# CH32X035F8U6-R0.net
KiCad netlist of a schematic drawn in Altium Designer
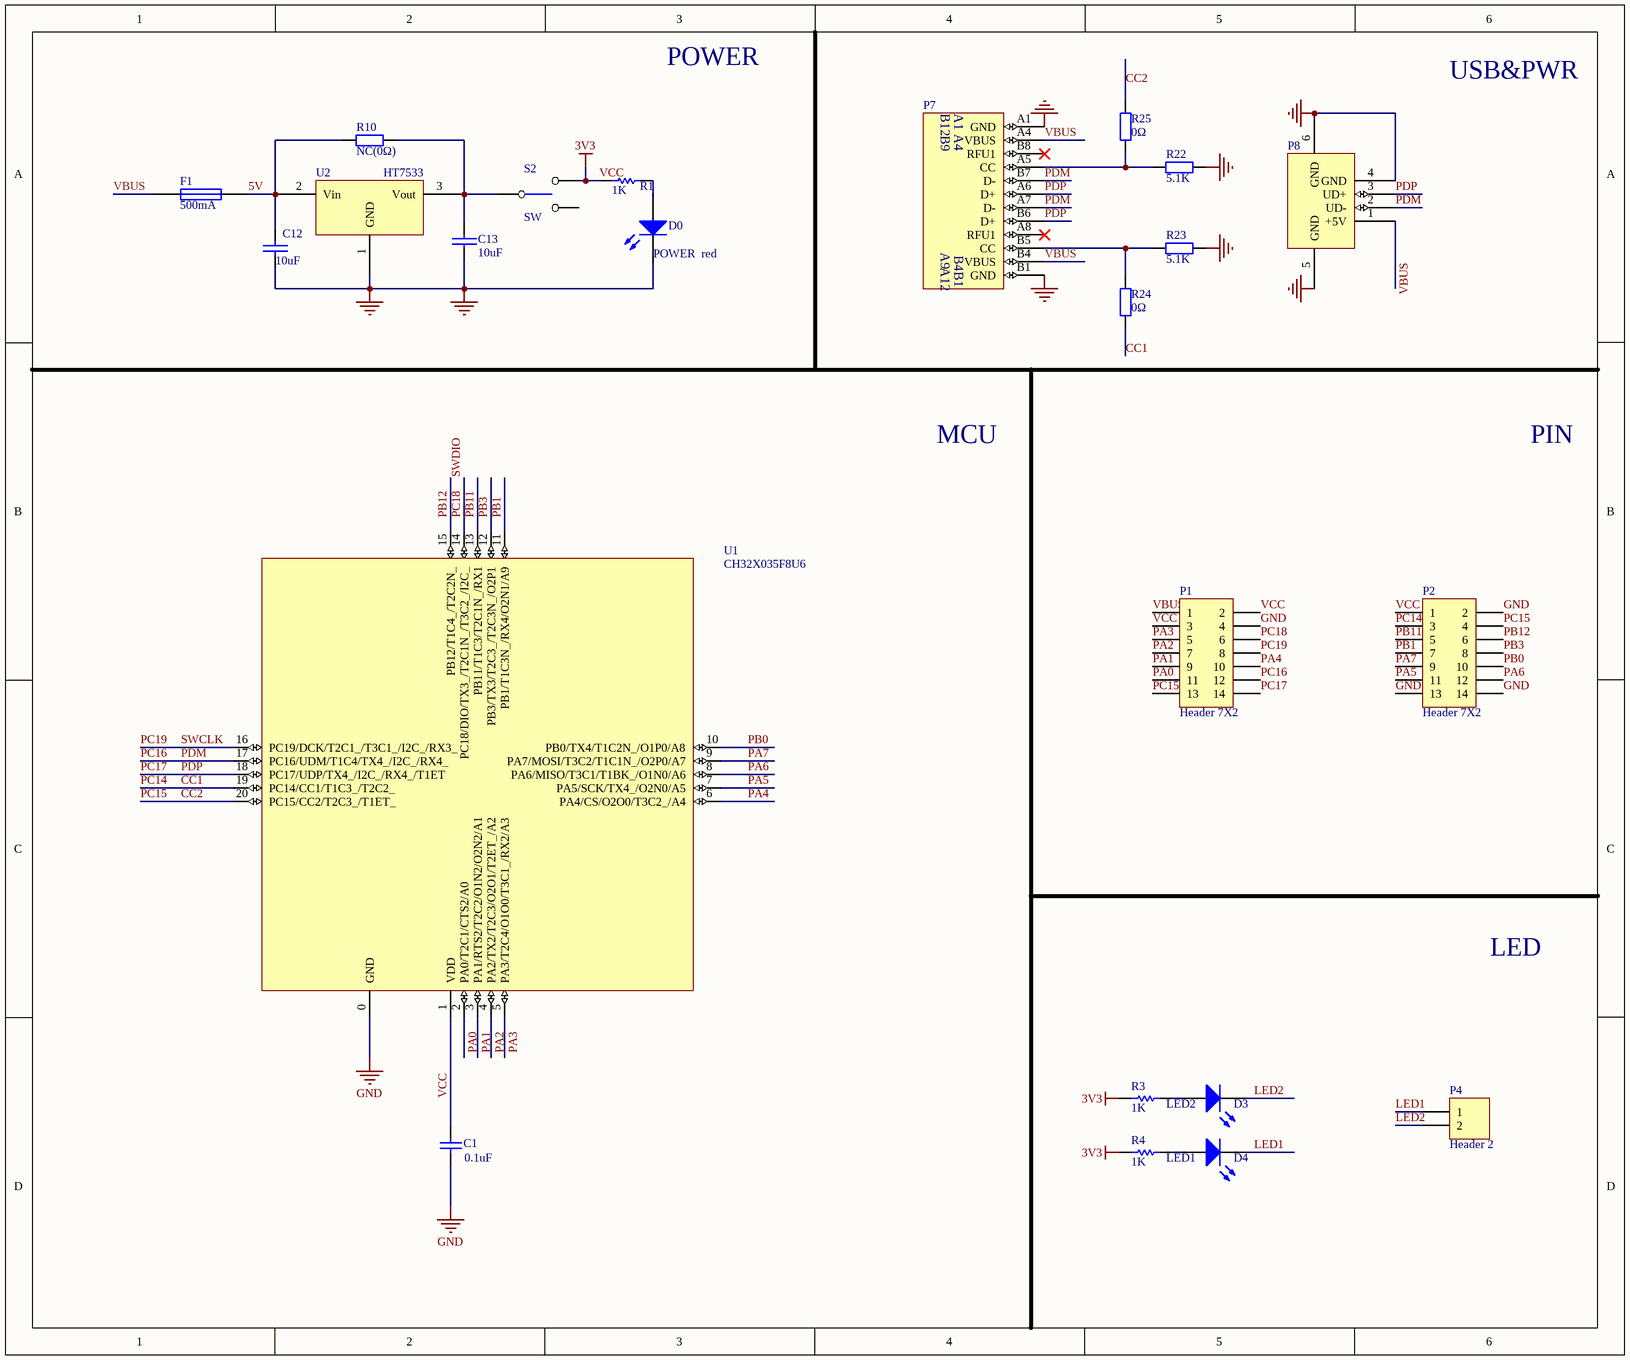
[diagram p0: CH32X035F8U6-R0.SchDoc]

(export (version "E")
  (design (tool "Eeschema 10.0.6"))
  (components
    (comp (ref "C1")
      (value "0.1uF")
      (footprint "0603_C")
      (description "Capacitor")
      (libsource (lib "Miscellaneous Devices") (part "Cap"))
    )
    (comp (ref "C12")
      (value "10uF")
      (footprint "0603_C")
      (description "Capacitor")
      (libsource (lib "*") (part "CAP"))
    )
    (comp (ref "C13")
      (value "10uF")
      (footprint "0603_C")
      (description "Capacitor")
      (libsource (lib "*") (part "CAP"))
    )
    (comp (ref "D0")
      (value "POWER  red")
      (footprint "0603+")
      (description "Typical INFRARED GaAs LED")
      (fields (field (name "PUBLISHER") "Altium Limited"))
      (libsource (lib "*") (part "LED0"))
    )
    (comp (ref "D3")
      (value "LED2")
      (footprint "0603+")
      (description "Typical INFRARED GaAs LED")
      (fields (field (name "PUBLISHER") "Altium Limited"))
      (libsource (lib "*") (part "LED0"))
    )
    (comp (ref "D4")
      (value "LED1")
      (footprint "0603+")
      (description "Typical INFRARED GaAs LED")
      (fields (field (name "PUBLISHER") "Altium Limited"))
      (libsource (lib "*") (part "LED0"))
    )
    (comp (ref "F1")
      (value "500mA")
      (footprint "0603")
      (description "Fuse")
      (libsource (lib "*") (part "FUSE1"))
    )
    (comp (ref "P1")
      (value "Header 7X2")
      (footprint "IDC14-2.54mm")
      (description "Header, 7-Pin, Dual row")
      (fields (field (name "PUBLISHER") "Altium Limited"))
      (libsource (lib "Miscellaneous Connectors") (part "Header 7X2"))
    )
    (comp (ref "P2")
      (value "Header 7X2")
      (footprint "IDC14-2.54mm")
      (description "Header, 7-Pin, Dual row")
      (fields (field (name "PUBLISHER") "Altium Limited"))
      (libsource (lib "Miscellaneous Connectors") (part "Header 7X2"))
    )
    (comp (ref "P4")
      (value "Header 2")
      (footprint "SIP2-2.54mm")
      (description "Header, 2-Pin")
      (fields (field (name "PUBLISHER") "Altium Limited"))
      (libsource (lib "Miscellaneous Connectors") (part "Header 2"))
    )
    (comp (ref "P7")
      (value "TYPE-C")
      (footprint "TYPE-C-Receptacle-2.0")
      (libsource (lib "*") (part "TYPE-C1"))
    )
    (comp (ref "P8")
      (value "USB_A")
      (footprint "USBAF")
      (description "USB Port")
      (libsource (lib "*") (part "USB"))
    )
    (comp (ref "R1")
      (value "1K")
      (footprint "0603")
      (description "Semiconductor Resistor")
      (fields (field (name "PUBLISHER") "Altium Limited"))
      (libsource (lib "*") (part "Res Semi"))
    )
    (comp (ref "R3")
      (value "1K")
      (footprint "0603")
      (description "Semiconductor Resistor")
      (fields (field (name "PUBLISHER") "Altium Limited"))
      (libsource (lib "*") (part "Res Semi"))
    )
    (comp (ref "R4")
      (value "1K")
      (footprint "0603")
      (description "Semiconductor Resistor")
      (fields (field (name "PUBLISHER") "Altium Limited"))
      (libsource (lib "*") (part "Res Semi"))
    )
    (comp (ref "R10")
      (value "NC(0Ω)")
      (footprint "0603")
      (description "Resistor")
      (fields (field (name "PUBLISHER") "Altium Limited"))
      (libsource (lib "*") (part "Res2"))
    )
    (comp (ref "R22")
      (value "5.1K")
      (footprint "0603")
      (description "Resistor")
      (libsource (lib "") (part "Res2_1"))
    )
    (comp (ref "R23")
      (value "5.1K")
      (footprint "0603")
      (description "Resistor")
      (libsource (lib "") (part "Res2_1"))
    )
    (comp (ref "R24")
      (value "0Ω")
      (footprint "0603")
      (description "Resistor")
      (libsource (lib "Miscellaneous Devices") (part "Res2"))
    )
    (comp (ref "R25")
      (value "0Ω")
      (footprint "0603")
      (description "Resistor")
      (libsource (lib "Miscellaneous Devices") (part "Res2"))
    )
    (comp (ref "S2") (value "SW") (footprint "SW1") (libsource (lib "*") (part "SW")))
    (comp (ref "U1")
      (value "CH32X035F8U6")
      (footprint "QFN20_3X3")
      (description "RISC-V MCU with USB/PD/ADC/SPI/I2C/UART/OA")
      (libsource (lib "CHXXX") (part "CH32X035F8U6"))
    )
    (comp (ref "U2")
      (value "HT7533")
      (footprint "SOT-89")
      (libsource (lib "wch_sch_others") (part "1117-3.3V"))
    )
  )
  (nets
    (net (code "1") (name "/5V") (class "Default")
      (node (ref "C12") (pin "1") (pinfunction "1_1") (pintype "passive"))
      (node (ref "F1") (pin "2") (pinfunction "2_2") (pintype "passive"))
      (node (ref "R10") (pin "2") (pinfunction "2_2") (pintype "passive"))
      (node (ref "U2") (pin "2") (pinfunction "Vin_2") (pintype "passive"))
    )
    (net (code "3") (name "/CC1") (class "Default")
      (node (ref "P2") (pin "3") (pinfunction "3_3") (pintype "passive"))
      (node (ref "R24") (pin "1") (pinfunction "1_1") (pintype "passive"))
      (node (ref "U1") (pin "19") (pinfunction "PC14/CC1/T1C3_/T2C2__19") (pintype "bidirectional"))
    )
    (net (code "4") (name "/CC2") (class "Default")
      (node (ref "P1") (pin "13") (pinfunction "13_13") (pintype "passive"))
      (node (ref "P2") (pin "4") (pinfunction "4_4") (pintype "passive"))
      (node (ref "R25") (pin "2") (pinfunction "2_2") (pintype "passive"))
      (node (ref "U1") (pin "20") (pinfunction "PC15/CC2/T2C3_/T1ET__20") (pintype "bidirectional"))
    )
    (net (code "5") (name "/LED1") (class "Default")
      (node (ref "D4") (pin "2") (pinfunction "K_2") (pintype "passive"))
      (node (ref "P4") (pin "1") (pinfunction "1_1") (pintype "passive"))
    )
    (net (code "6") (name "/LED2") (class "Default")
      (node (ref "D3") (pin "2") (pinfunction "K_2") (pintype "passive"))
      (node (ref "P4") (pin "2") (pinfunction "2_2") (pintype "passive"))
    )
    (net (code "7") (name "/PA0") (class "Default")
      (node (ref "P1") (pin "11") (pinfunction "11_11") (pintype "passive"))
      (node (ref "U1") (pin "2") (pinfunction "PA0/T2C1/CTS2/A0_2") (pintype "bidirectional"))
    )
    (net (code "8") (name "/PA1") (class "Default")
      (node (ref "P1") (pin "9") (pinfunction "9_9") (pintype "passive"))
      (node (ref "U1") (pin "3") (pinfunction "PA1/RTS2/T2C2/O1N2/O2N2/A1_3") (pintype "bidirectional"))
    )
    (net (code "9") (name "/PA2") (class "Default")
      (node (ref "P1") (pin "7") (pinfunction "7_7") (pintype "passive"))
      (node (ref "U1") (pin "4") (pinfunction "PA2/TX2/T2C3/O2O1/T2ET_/A2_4") (pintype "bidirectional"))
    )
    (net (code "10") (name "/PA3") (class "Default")
      (node (ref "P1") (pin "5") (pinfunction "5_5") (pintype "passive"))
      (node (ref "U1") (pin "5") (pinfunction "PA3/T2C4/O1O0/T3C1_/RX2/A3_5") (pintype "bidirectional"))
    )
    (net (code "11") (name "/PA4") (class "Default")
      (node (ref "P1") (pin "10") (pinfunction "10_10") (pintype "passive"))
      (node (ref "U1") (pin "6") (pinfunction "PA4/CS/O2O0/T3C2_/A4_6") (pintype "bidirectional"))
    )
    (net (code "12") (name "/PA5") (class "Default")
      (node (ref "P2") (pin "11") (pinfunction "11_11") (pintype "passive"))
      (node (ref "U1") (pin "7") (pinfunction "PA5/SCK/TX4_/O2N0/A5_7") (pintype "bidirectional"))
    )
    (net (code "13") (name "/PA6") (class "Default")
      (node (ref "P2") (pin "12") (pinfunction "12_12") (pintype "passive"))
      (node (ref "U1") (pin "8") (pinfunction "PA6/MISO/T3C1/T1BK_/O1N0/A6_8") (pintype "bidirectional"))
    )
    (net (code "14") (name "/PA7") (class "Default")
      (node (ref "P2") (pin "9") (pinfunction "9_9") (pintype "passive"))
      (node (ref "U1") (pin "9") (pinfunction "PA7/MOSI/T3C2/T1C1N_/O2P0/A7_9") (pintype "bidirectional"))
    )
    (net (code "15") (name "/PB0") (class "Default")
      (node (ref "P2") (pin "10") (pinfunction "10_10") (pintype "passive"))
      (node (ref "U1") (pin "10") (pinfunction "PB0/TX4/T1C2N_/O1P0/A8_10") (pintype "bidirectional"))
    )
    (net (code "16") (name "/PB1") (class "Default")
      (node (ref "P2") (pin "7") (pinfunction "7_7") (pintype "passive"))
      (node (ref "U1") (pin "11") (pinfunction "PB1/T1C3N_/RX4/O2N1/A9_11") (pintype "bidirectional"))
    )
    (net (code "17") (name "/PB3") (class "Default")
      (node (ref "P2") (pin "8") (pinfunction "8_8") (pintype "passive"))
      (node (ref "U1") (pin "12") (pinfunction "PB3/TX3/T2C3_/T2C3N_/O2P1_12") (pintype "bidirectional"))
    )
    (net (code "18") (name "/PB11") (class "Default")
      (node (ref "P2") (pin "5") (pinfunction "5_5") (pintype "passive"))
      (node (ref "U1") (pin "13") (pinfunction "PB11/T1C3/T2C1N_/RX1_13") (pintype "bidirectional"))
    )
    (net (code "19") (name "/PB12") (class "Default")
      (node (ref "P2") (pin "6") (pinfunction "6_6") (pintype "passive"))
      (node (ref "U1") (pin "15") (pinfunction "PB12/T1C4_/T2C2N__15") (pintype "bidirectional"))
    )
    (net (code "20") (name "/PC16") (class "Default")
      (node (ref "P1") (pin "12") (pinfunction "12_12") (pintype "passive"))
      (node (ref "P7") (pin "A7") (pinfunction "D-_A7") (pintype "bidirectional"))
      (node (ref "P7") (pin "B7") (pinfunction "D-_B7") (pintype "bidirectional"))
      (node (ref "P8") (pin "2") (pinfunction "UD-_2") (pintype "bidirectional"))
      (node (ref "U1") (pin "17") (pinfunction "PC16/UDM/T1C4/TX4_/I2C_/RX4__17") (pintype "bidirectional"))
    )
    (net (code "21") (name "/PC17") (class "Default")
      (node (ref "P1") (pin "14") (pinfunction "14_14") (pintype "passive"))
      (node (ref "P7") (pin "A6") (pinfunction "D+_A6") (pintype "bidirectional"))
      (node (ref "P7") (pin "B6") (pinfunction "D+_B6") (pintype "bidirectional"))
      (node (ref "P8") (pin "3") (pinfunction "UD+_3") (pintype "bidirectional"))
      (node (ref "U1") (pin "18") (pinfunction "PC17/UDP/TX4_/I2C_/RX4_/T1ET_18") (pintype "bidirectional"))
    )
    (net (code "22") (name "/PC18") (class "Default")
      (node (ref "P1") (pin "6") (pinfunction "6_6") (pintype "passive"))
      (node (ref "U1") (pin "14") (pinfunction "PC18/DIO/TX3_/T2C1N_/T3C2_/I2C__14") (pintype "bidirectional"))
    )
    (net (code "23") (name "/PC19") (class "Default")
      (node (ref "P1") (pin "8") (pinfunction "8_8") (pintype "passive"))
      (node (ref "U1") (pin "16") (pinfunction "PC19/DCK/T2C1_/T3C1_/I2C_/RX3__16") (pintype "bidirectional"))
    )
    (net (code "24") (name "/VBUS") (class "Default")
      (node (ref "F1") (pin "1") (pinfunction "1_1") (pintype "passive"))
      (node (ref "P1") (pin "1") (pinfunction "1_1") (pintype "passive"))
      (node (ref "P7") (pin "A4") (pinfunction "VBUS_A4") (pintype "bidirectional"))
      (node (ref "P7") (pin "B4") (pinfunction "VBUS_B4") (pintype "bidirectional"))
      (node (ref "P8") (pin "1") (pinfunction "+5V_1") (pintype "power_in"))
    )
    (net (code "25") (name "3V3") (class "Default")
      (node (ref "C1") (pin "2") (pinfunction "2_2") (pintype "passive"))
      (node (ref "P1") (pin "2") (pinfunction "2_2") (pintype "passive"))
      (node (ref "P1") (pin "3") (pinfunction "3_3") (pintype "passive"))
      (node (ref "P2") (pin "1") (pinfunction "1_1") (pintype "passive"))
      (node (ref "R1") (pin "2") (pinfunction "2_2") (pintype "passive"))
      (node (ref "R3") (pin "1") (pinfunction "1_1") (pintype "passive"))
      (node (ref "R4") (pin "1") (pinfunction "1_1") (pintype "passive"))
      (node (ref "S2") (pin "3") (pinfunction "3_3") (pintype "passive"))
      (node (ref "U1") (pin "1") (pinfunction "VDD_1") (pintype "power_in"))
    )
    (net (code "26") (name "GND") (class "Default")
      (node (ref "C1") (pin "1") (pinfunction "1_1") (pintype "passive"))
      (node (ref "C12") (pin "2") (pinfunction "2_2") (pintype "passive"))
      (node (ref "C13") (pin "2") (pinfunction "2_2") (pintype "passive"))
      (node (ref "D0") (pin "2") (pinfunction "K_2") (pintype "passive"))
      (node (ref "P1") (pin "4") (pinfunction "4_4") (pintype "passive"))
      (node (ref "P2") (pin "13") (pinfunction "13_13") (pintype "passive"))
      (node (ref "P2") (pin "14") (pinfunction "14_14") (pintype "passive"))
      (node (ref "P2") (pin "2") (pinfunction "2_2") (pintype "passive"))
      (node (ref "P7") (pin "A1") (pinfunction "GND_A1") (pintype "bidirectional"))
      (node (ref "P7") (pin "B1") (pinfunction "GND_B1") (pintype "bidirectional"))
      (node (ref "P8") (pin "4") (pinfunction "GND_4") (pintype "power_in"))
      (node (ref "P8") (pin "5") (pinfunction "GND_5") (pintype "power_in"))
      (node (ref "P8") (pin "6") (pinfunction "GND_6") (pintype "power_in"))
      (node (ref "R22") (pin "2") (pinfunction "2_2") (pintype "passive"))
      (node (ref "R23") (pin "2") (pinfunction "2_2") (pintype "passive"))
      (node (ref "U1") (pin "0") (pinfunction "GND_0") (pintype "power_in"))
      (node (ref "U2") (pin "1") (pinfunction "GND_1") (pintype "passive"))
    )
    (net (code "27") (name "Net-(D0-A)") (class "Default")
      (node (ref "D0") (pin "1") (pinfunction "A_1") (pintype "passive"))
      (node (ref "R1") (pin "1") (pinfunction "1_1") (pintype "passive"))
    )
    (net (code "28") (name "Net-(D3-A)") (class "Default")
      (node (ref "D3") (pin "1") (pinfunction "A_1") (pintype "passive"))
      (node (ref "R3") (pin "2") (pinfunction "2_2") (pintype "passive"))
    )
    (net (code "29") (name "Net-(D4-A)") (class "Default")
      (node (ref "D4") (pin "1") (pinfunction "A_1") (pintype "passive"))
      (node (ref "R4") (pin "2") (pinfunction "2_2") (pintype "passive"))
    )
    (net (code "30") (name "Net-(P7-CC-PadA5)") (class "Default")
      (node (ref "P7") (pin "A5") (pinfunction "CC_A5") (pintype "bidirectional"))
      (node (ref "R22") (pin "1") (pinfunction "1_1") (pintype "passive"))
      (node (ref "R25") (pin "1") (pinfunction "1_1") (pintype "passive"))
    )
    (net (code "31") (name "Net-(P7-CC-PadB5)") (class "Default")
      (node (ref "P7") (pin "B5") (pinfunction "CC_B5") (pintype "bidirectional"))
      (node (ref "R23") (pin "1") (pinfunction "1_1") (pintype "passive"))
      (node (ref "R24") (pin "2") (pinfunction "2_2") (pintype "passive"))
    )
    (net (code "32") (name "Net-(U2-Vout)") (class "Default")
      (node (ref "C13") (pin "1") (pinfunction "1_1") (pintype "passive"))
      (node (ref "R10") (pin "1") (pinfunction "1_1") (pintype "passive"))
      (node (ref "S2") (pin "1") (pinfunction "1_1") (pintype "passive"))
      (node (ref "U2") (pin "3") (pinfunction "Vout_3") (pintype "passive"))
    )
    (net (code "33") (name "unconnected-(P7-RFU1-PadA8)") (class "Default")
      (node (ref "P7") (pin "A8") (pinfunction "RFU1_A8") (pintype "bidirectional+no_connect"))
    )
    (net (code "34") (name "unconnected-(P7-RFU1-PadB8)") (class "Default")
      (node (ref "P7") (pin "B8") (pinfunction "RFU1_B8") (pintype "bidirectional+no_connect"))
    )
    (net (code "35") (name "unconnected-(S2-Pad2)") (class "Default")
      (node (ref "S2") (pin "2") (pinfunction "2_2") (pintype "passive"))
    )
  )
)
